# RotaryEncoderModule_r1_1.net
KiCad netlist of a schematic drawn in EAGLE
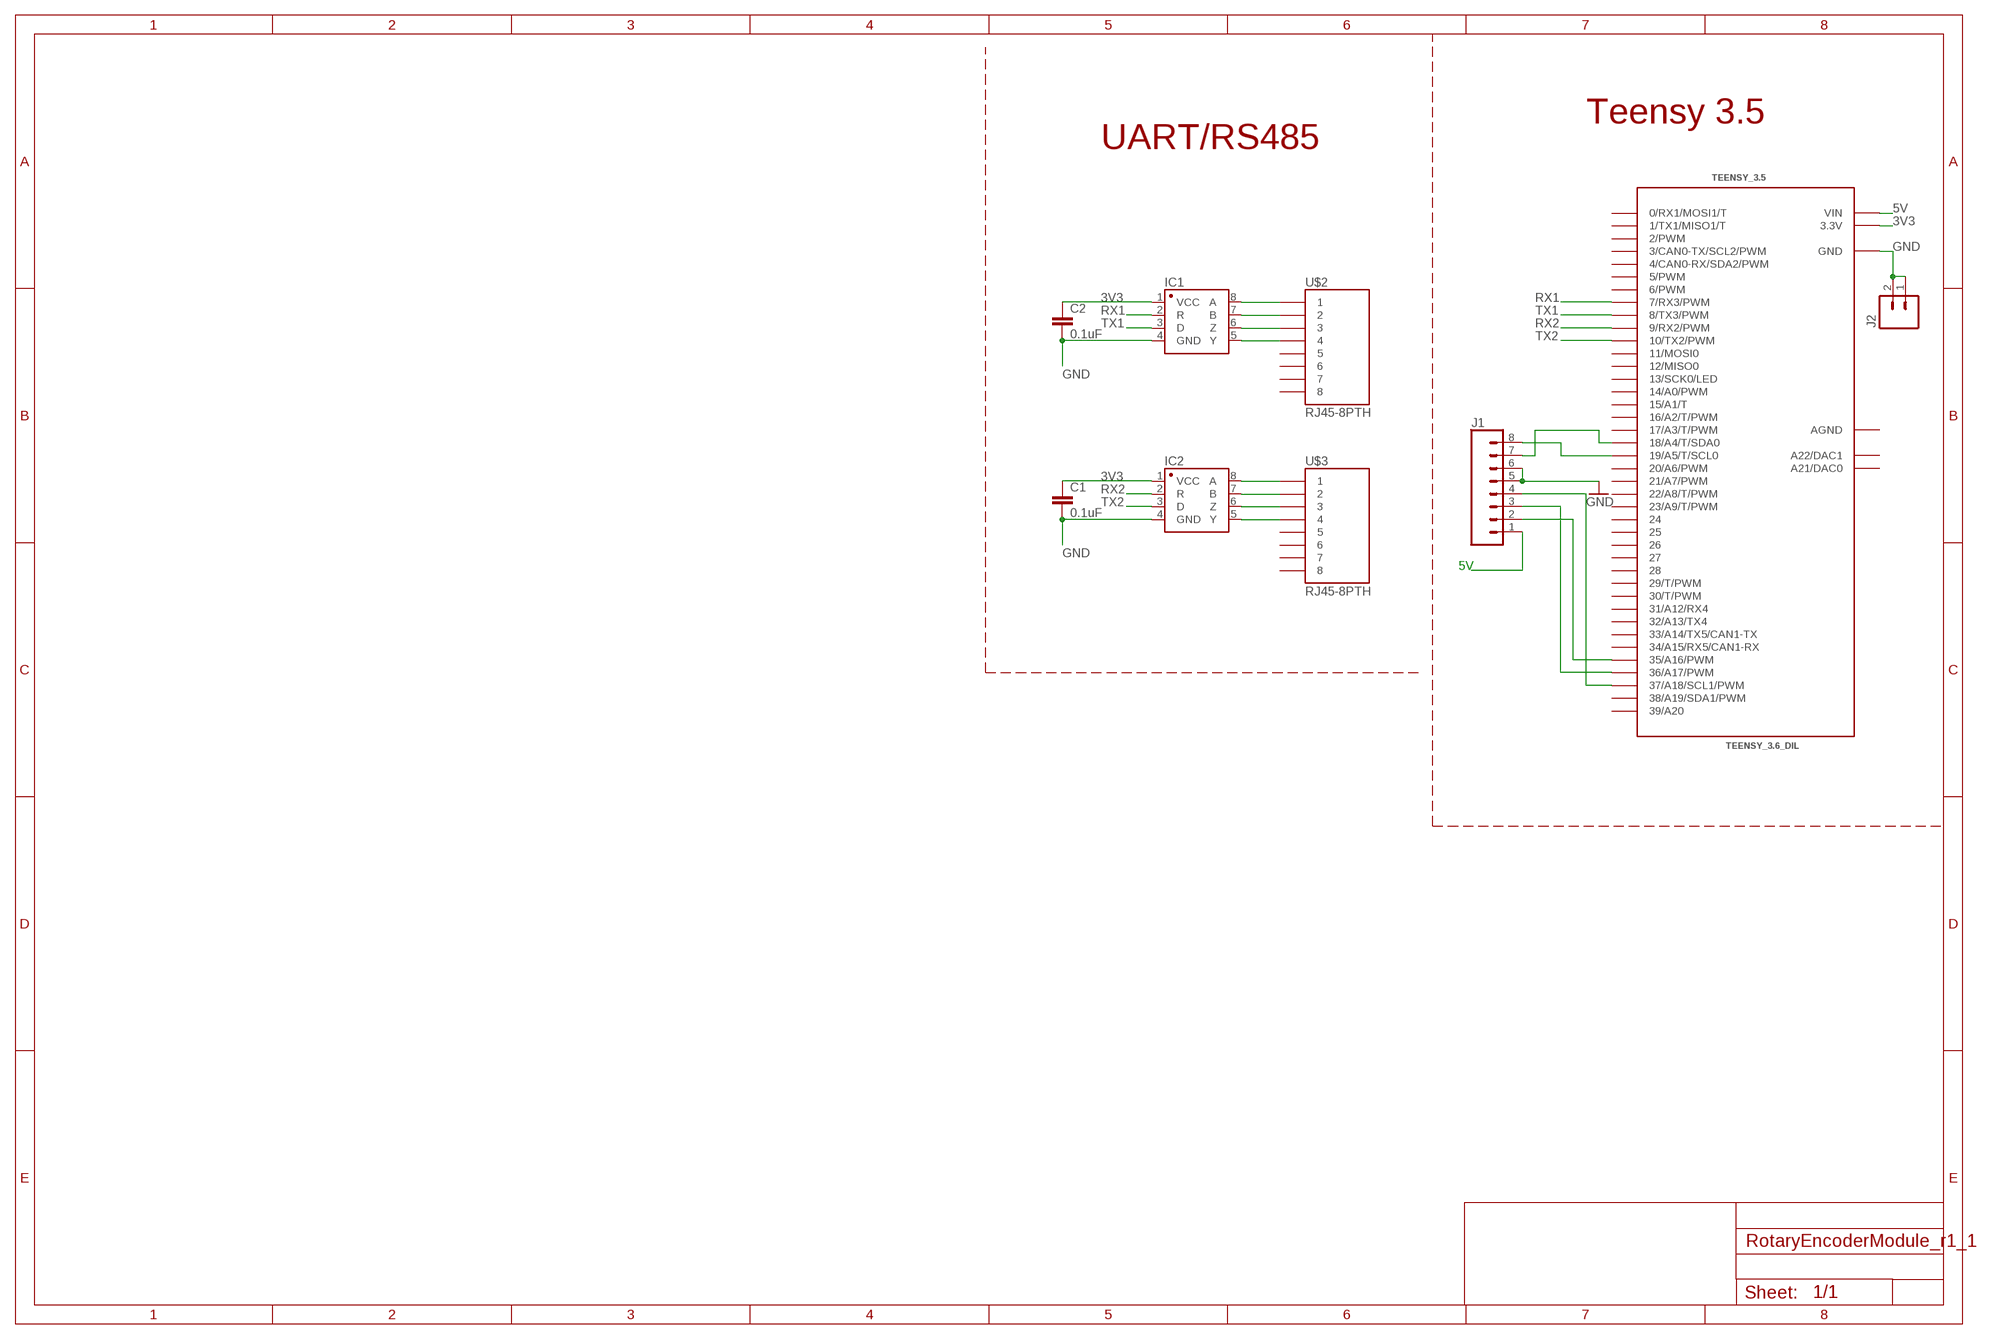
[diagram p0: schematic, sheet 1]

(export (version "E")
  (design (tool "Eeschema 10.0.6"))
  (components
    (comp (ref "C1")
      (value "0.1uF")
      (footprint "eagle-import:1206")
      (libsource (lib "eagle-import") (part "1.0UF-1206-50V-10%"))
    )
    (comp (ref "C2")
      (value "0.1uF")
      (footprint "eagle-import:1206")
      (libsource (lib "eagle-import") (part "1.0UF-1206-50V-10%"))
    )
    (comp (ref "IC1")
      (value "SN65HVD31DR")
      (footprint "eagle-import:SO08")
      (libsource (lib "eagle-import") (part "SN65HVD31DR"))
    )
    (comp (ref "IC2")
      (value "SN65HVD31DR")
      (footprint "eagle-import:SO08")
      (libsource (lib "eagle-import") (part "SN65HVD31DR"))
    )
    (comp (ref "J1")
      (value "CONN_083.5MM-8")
      (footprint "eagle-import:SCREWTERMINAL-3.5MM-8")
      (libsource (lib "eagle-import") (part "CONN_083.5MM-8"))
    )
    (comp (ref "J2")
      (value "M023.5MM")
      (footprint "eagle-import:SCREWTERMINAL-3.5MM-2")
      (libsource (lib "eagle-import") (part "M023.5MM"))
    )
    (comp (ref "TEENSY_3.5")
      (value "TEENSY_3.6_DIL")
      (footprint "eagle-import:TEENSY_3.6_DIL")
      (libsource (lib "eagle-import") (part "TEENSY_3.6_DIL"))
    )
    (comp (ref "U$2")
      (value "RJ45-8PTH")
      (footprint "eagle-import:RJ45-8")
      (libsource (lib "eagle-import") (part "RJ45-8PTH"))
    )
    (comp (ref "U$3")
      (value "RJ45-8PTH")
      (footprint "eagle-import:RJ45-8")
      (libsource (lib "eagle-import") (part "RJ45-8PTH"))
    )
  )
  (nets
    (net (code "1") (name "/3V3") (class "Default")
      (node (ref "C1") (pin "1") (pinfunction "1_1") (pintype "passive"))
      (node (ref "C2") (pin "1") (pinfunction "1_1") (pintype "passive"))
      (node (ref "IC1") (pin "1") (pinfunction "VCC_1") (pintype "bidirectional"))
      (node (ref "IC2") (pin "1") (pinfunction "VCC_1") (pintype "bidirectional"))
      (node (ref "TEENSY_3.5") (pin "3.3V") (pinfunction "3.3V_3.3V") (pintype "power_in"))
      (node (ref "TEENSY_3.5") (pin "3.3V3") (pinfunction "3.3V_3.3V3") (pintype "power_in"))
    )
    (net (code "2") (name "/5V") (class "Default")
      (node (ref "J1") (pin "1") (pinfunction "1_1") (pintype "passive"))
      (node (ref "TEENSY_3.5") (pin "VIN") (pinfunction "VIN_VIN") (pintype "power_in"))
    )
    (net (code "3") (name "/AGND") (class "Default")
      (node (ref "TEENSY_3.5") (pin "AGND") (pinfunction "AGND_AGND") (pintype "power_in"))
    )
    (net (code "4") (name "/RX1") (class "Default")
      (node (ref "IC1") (pin "2") (pinfunction "R_2") (pintype "bidirectional"))
      (node (ref "TEENSY_3.5") (pin "7") (pinfunction "7/RX3/PWM_7") (pintype "bidirectional"))
    )
    (net (code "5") (name "/RX2") (class "Default")
      (node (ref "IC2") (pin "2") (pinfunction "R_2") (pintype "bidirectional"))
      (node (ref "TEENSY_3.5") (pin "9") (pinfunction "9/RX2/PWM_9") (pintype "bidirectional"))
    )
    (net (code "6") (name "/TX1") (class "Default")
      (node (ref "IC1") (pin "3") (pinfunction "D_3") (pintype "bidirectional"))
      (node (ref "TEENSY_3.5") (pin "8") (pinfunction "8/TX3/PWM_8") (pintype "bidirectional"))
    )
    (net (code "7") (name "/TX2") (class "Default")
      (node (ref "IC2") (pin "3") (pinfunction "D_3") (pintype "bidirectional"))
      (node (ref "TEENSY_3.5") (pin "10") (pinfunction "10/TX2/PWM_10") (pintype "bidirectional"))
    )
    (net (code "8") (name "GND") (class "Default")
      (node (ref "C1") (pin "2") (pinfunction "2_2") (pintype "passive"))
      (node (ref "C2") (pin "2") (pinfunction "2_2") (pintype "passive"))
      (node (ref "IC1") (pin "4") (pinfunction "GND_4") (pintype "bidirectional"))
      (node (ref "IC2") (pin "4") (pinfunction "GND_4") (pintype "bidirectional"))
      (node (ref "J1") (pin "5") (pinfunction "5_5") (pintype "passive"))
      (node (ref "J1") (pin "6") (pinfunction "6_6") (pintype "passive"))
      (node (ref "J2") (pin "1") (pinfunction "1_1") (pintype "passive"))
      (node (ref "J2") (pin "2") (pinfunction "2_2") (pintype "passive"))
      (node (ref "TEENSY_3.5") (pin "GND") (pinfunction "GND_GND") (pintype "power_in"))
      (node (ref "TEENSY_3.5") (pin "GND1") (pinfunction "GND_GND1") (pintype "power_in"))
    )
    (net (code "9") (name "Net-(IC1-A)") (class "Default")
      (node (ref "IC1") (pin "8") (pinfunction "A_8") (pintype "bidirectional"))
      (node (ref "U$2") (pin "1") (pinfunction "1_1") (pintype "bidirectional"))
    )
    (net (code "10") (name "Net-(IC1-B)") (class "Default")
      (node (ref "IC1") (pin "7") (pinfunction "B_7") (pintype "bidirectional"))
      (node (ref "U$2") (pin "2") (pinfunction "2_2") (pintype "bidirectional"))
    )
    (net (code "11") (name "Net-(IC1-Y)") (class "Default")
      (node (ref "IC1") (pin "5") (pinfunction "Y_5") (pintype "bidirectional"))
      (node (ref "U$2") (pin "4") (pinfunction "4_4") (pintype "bidirectional"))
    )
    (net (code "12") (name "Net-(IC1-Z)") (class "Default")
      (node (ref "IC1") (pin "6") (pinfunction "Z_6") (pintype "bidirectional"))
      (node (ref "U$2") (pin "3") (pinfunction "3_3") (pintype "bidirectional"))
    )
    (net (code "13") (name "Net-(IC2-A)") (class "Default")
      (node (ref "IC2") (pin "8") (pinfunction "A_8") (pintype "bidirectional"))
      (node (ref "U$3") (pin "1") (pinfunction "1_1") (pintype "bidirectional"))
    )
    (net (code "14") (name "Net-(IC2-B)") (class "Default")
      (node (ref "IC2") (pin "7") (pinfunction "B_7") (pintype "bidirectional"))
      (node (ref "U$3") (pin "2") (pinfunction "2_2") (pintype "bidirectional"))
    )
    (net (code "15") (name "Net-(IC2-Y)") (class "Default")
      (node (ref "IC2") (pin "5") (pinfunction "Y_5") (pintype "bidirectional"))
      (node (ref "U$3") (pin "4") (pinfunction "4_4") (pintype "bidirectional"))
    )
    (net (code "16") (name "Net-(IC2-Z)") (class "Default")
      (node (ref "IC2") (pin "6") (pinfunction "Z_6") (pintype "bidirectional"))
      (node (ref "U$3") (pin "3") (pinfunction "3_3") (pintype "bidirectional"))
    )
    (net (code "17") (name "Net-(TEENSY_3.5-18{slash}A4{slash}T{slash}SDA0)") (class "Default")
      (node (ref "J1") (pin "7") (pinfunction "7_7") (pintype "passive"))
      (node (ref "TEENSY_3.5") (pin "18/A4") (pinfunction "18/A4/T/SDA0_18/A4") (pintype "bidirectional"))
    )
    (net (code "18") (name "Net-(TEENSY_3.5-19{slash}A5{slash}T{slash}SCL0)") (class "Default")
      (node (ref "J1") (pin "8") (pinfunction "8_8") (pintype "passive"))
      (node (ref "TEENSY_3.5") (pin "19/A5") (pinfunction "19/A5/T/SCL0_19/A5") (pintype "bidirectional"))
    )
    (net (code "19") (name "Net-(TEENSY_3.5-35{slash}A16{slash}PWM)") (class "Default")
      (node (ref "J1") (pin "2") (pinfunction "2_2") (pintype "passive"))
      (node (ref "TEENSY_3.5") (pin "35/A16") (pinfunction "35/A16/PWM_35/A16") (pintype "bidirectional"))
    )
    (net (code "20") (name "Net-(TEENSY_3.5-36{slash}A17{slash}PWM)") (class "Default")
      (node (ref "J1") (pin "3") (pinfunction "3_3") (pintype "passive"))
      (node (ref "TEENSY_3.5") (pin "36/A17") (pinfunction "36/A17/PWM_36/A17") (pintype "bidirectional"))
    )
    (net (code "21") (name "Net-(TEENSY_3.5-37{slash}A18{slash}SCL1{slash}PWM)") (class "Default")
      (node (ref "J1") (pin "4") (pinfunction "4_4") (pintype "passive"))
      (node (ref "TEENSY_3.5") (pin "37/A18") (pinfunction "37/A18/SCL1/PWM_37/A18") (pintype "bidirectional"))
    )
    (net (code "22") (name "unconnected-(TEENSY_3.5-0{slash}RX1{slash}MOSI1{slash}T-Pad0)") (class "Default")
      (node (ref "TEENSY_3.5") (pin "0") (pinfunction "0/RX1/MOSI1/T_0") (pintype "bidirectional"))
    )
    (net (code "23") (name "unconnected-(TEENSY_3.5-1{slash}TX1{slash}MISO1{slash}T-Pad1)") (class "Default")
      (node (ref "TEENSY_3.5") (pin "1") (pinfunction "1/TX1/MISO1/T_1") (pintype "bidirectional"))
    )
    (net (code "24") (name "unconnected-(TEENSY_3.5-2{slash}PWM-Pad2)") (class "Default")
      (node (ref "TEENSY_3.5") (pin "2") (pinfunction "2/PWM_2") (pintype "bidirectional"))
    )
    (net (code "25") (name "unconnected-(TEENSY_3.5-3{slash}CAN0-TX{slash}SCL2{slash}PWM-Pad3)") (class "Default")
      (node (ref "TEENSY_3.5") (pin "3") (pinfunction "3/CAN0-TX/SCL2/PWM_3") (pintype "bidirectional"))
    )
    (net (code "26") (name "unconnected-(TEENSY_3.5-4{slash}CAN0-RX{slash}SDA2{slash}PWM-Pad4)") (class "Default")
      (node (ref "TEENSY_3.5") (pin "4") (pinfunction "4/CAN0-RX/SDA2/PWM_4") (pintype "bidirectional"))
    )
    (net (code "27") (name "unconnected-(TEENSY_3.5-5{slash}PWM-Pad5)") (class "Default")
      (node (ref "TEENSY_3.5") (pin "5") (pinfunction "5/PWM_5") (pintype "bidirectional"))
    )
    (net (code "28") (name "unconnected-(TEENSY_3.5-6{slash}PWM-Pad6)") (class "Default")
      (node (ref "TEENSY_3.5") (pin "6") (pinfunction "6/PWM_6") (pintype "bidirectional"))
    )
    (net (code "29") (name "unconnected-(TEENSY_3.5-11{slash}MOSI0-Pad11)") (class "Default")
      (node (ref "TEENSY_3.5") (pin "11") (pinfunction "11/MOSI0_11") (pintype "bidirectional"))
    )
    (net (code "30") (name "unconnected-(TEENSY_3.5-12{slash}MISO0-Pad12)") (class "Default")
      (node (ref "TEENSY_3.5") (pin "12") (pinfunction "12/MISO0_12") (pintype "bidirectional"))
    )
    (net (code "31") (name "unconnected-(TEENSY_3.5-13{slash}SCK0{slash}LED-Pad13)") (class "Default")
      (node (ref "TEENSY_3.5") (pin "13") (pinfunction "13/SCK0/LED_13") (pintype "bidirectional"))
    )
    (net (code "32") (name "unconnected-(TEENSY_3.5-14{slash}A0{slash}PWM-Pad14{slash}A0)") (class "Default")
      (node (ref "TEENSY_3.5") (pin "14/A0") (pinfunction "14/A0/PWM_14/A0") (pintype "bidirectional"))
    )
    (net (code "33") (name "unconnected-(TEENSY_3.5-15{slash}A1{slash}T-Pad15{slash}A1)") (class "Default")
      (node (ref "TEENSY_3.5") (pin "15/A1") (pinfunction "15/A1/T_15/A1") (pintype "bidirectional"))
    )
    (net (code "34") (name "unconnected-(TEENSY_3.5-16{slash}A2{slash}T{slash}PWM-Pad16{slash}A2)") (class "Default")
      (node (ref "TEENSY_3.5") (pin "16/A2") (pinfunction "16/A2/T/PWM_16/A2") (pintype "bidirectional"))
    )
    (net (code "35") (name "unconnected-(TEENSY_3.5-17{slash}A3{slash}T{slash}PWM-Pad17{slash}A3)") (class "Default")
      (node (ref "TEENSY_3.5") (pin "17/A3") (pinfunction "17/A3/T/PWM_17/A3") (pintype "bidirectional"))
    )
    (net (code "36") (name "unconnected-(TEENSY_3.5-20{slash}A6{slash}PWM-Pad20{slash}A6)") (class "Default")
      (node (ref "TEENSY_3.5") (pin "20/A6") (pinfunction "20/A6/PWM_20/A6") (pintype "bidirectional"))
    )
    (net (code "37") (name "unconnected-(TEENSY_3.5-21{slash}A7{slash}PWM-Pad21{slash}A7)") (class "Default")
      (node (ref "TEENSY_3.5") (pin "21/A7") (pinfunction "21/A7/PWM_21/A7") (pintype "bidirectional"))
    )
    (net (code "38") (name "unconnected-(TEENSY_3.5-22{slash}A8{slash}T{slash}PWM-Pad22{slash}A8)") (class "Default")
      (node (ref "TEENSY_3.5") (pin "22/A8") (pinfunction "22/A8/T/PWM_22/A8") (pintype "bidirectional"))
    )
    (net (code "39") (name "unconnected-(TEENSY_3.5-23{slash}A9{slash}T{slash}PWM-Pad23{slash}A9)") (class "Default")
      (node (ref "TEENSY_3.5") (pin "23/A9") (pinfunction "23/A9/T/PWM_23/A9") (pintype "bidirectional"))
    )
    (net (code "40") (name "unconnected-(TEENSY_3.5-29{slash}T{slash}PWM-Pad29)") (class "Default")
      (node (ref "TEENSY_3.5") (pin "29") (pinfunction "29/T/PWM_29") (pintype "bidirectional"))
    )
    (net (code "41") (name "unconnected-(TEENSY_3.5-30{slash}T{slash}PWM-Pad30)") (class "Default")
      (node (ref "TEENSY_3.5") (pin "30") (pinfunction "30/T/PWM_30") (pintype "bidirectional"))
    )
    (net (code "42") (name "unconnected-(TEENSY_3.5-31{slash}A12{slash}RX4-Pad31{slash}A12)") (class "Default")
      (node (ref "TEENSY_3.5") (pin "31/A12") (pinfunction "31/A12/RX4_31/A12") (pintype "bidirectional"))
    )
    (net (code "43") (name "unconnected-(TEENSY_3.5-32{slash}A13{slash}TX4-Pad32{slash}A13)") (class "Default")
      (node (ref "TEENSY_3.5") (pin "32/A13") (pinfunction "32/A13/TX4_32/A13") (pintype "bidirectional"))
    )
    (net (code "44") (name "unconnected-(TEENSY_3.5-33{slash}A14{slash}TX5{slash}CAN1-TX-Pad33{slash}A14)") (class "Default")
      (node (ref "TEENSY_3.5") (pin "33/A14") (pinfunction "33/A14/TX5/CAN1-TX_33/A14") (pintype "bidirectional"))
    )
    (net (code "45") (name "unconnected-(TEENSY_3.5-34{slash}A15{slash}RX5{slash}CAN1-RX-Pad34{slash}A15)") (class "Default")
      (node (ref "TEENSY_3.5") (pin "34/A15") (pinfunction "34/A15/RX5/CAN1-RX_34/A15") (pintype "bidirectional"))
    )
    (net (code "46") (name "unconnected-(TEENSY_3.5-38{slash}A19{slash}SDA1{slash}PWM-Pad38{slash}A19)") (class "Default")
      (node (ref "TEENSY_3.5") (pin "38/A19") (pinfunction "38/A19/SDA1/PWM_38/A19") (pintype "bidirectional"))
    )
    (net (code "47") (name "unconnected-(TEENSY_3.5-A21{slash}DAC0-PadA21)") (class "Default")
      (node (ref "TEENSY_3.5") (pin "A21") (pinfunction "A21/DAC0_A21") (pintype "bidirectional"))
    )
    (net (code "48") (name "unconnected-(TEENSY_3.5-A22{slash}DAC1-PadA22)") (class "Default")
      (node (ref "TEENSY_3.5") (pin "A22") (pinfunction "A22/DAC1_A22") (pintype "bidirectional"))
    )
    (net (code "49") (name "unconnected-(TEENSY_3.5-Pad24)") (class "Default")
      (node (ref "TEENSY_3.5") (pin "24") (pinfunction "24_24") (pintype "bidirectional"))
    )
    (net (code "50") (name "unconnected-(TEENSY_3.5-Pad25)") (class "Default")
      (node (ref "TEENSY_3.5") (pin "25") (pinfunction "25_25") (pintype "bidirectional"))
    )
    (net (code "51") (name "unconnected-(TEENSY_3.5-Pad26)") (class "Default")
      (node (ref "TEENSY_3.5") (pin "26") (pinfunction "26_26") (pintype "bidirectional"))
    )
    (net (code "52") (name "unconnected-(TEENSY_3.5-Pad27)") (class "Default")
      (node (ref "TEENSY_3.5") (pin "27") (pinfunction "27_27") (pintype "bidirectional"))
    )
    (net (code "53") (name "unconnected-(TEENSY_3.5-Pad28)") (class "Default")
      (node (ref "TEENSY_3.5") (pin "28") (pinfunction "28_28") (pintype "bidirectional"))
    )
    (net (code "54") (name "unconnected-(TEENSY_3.5-Pad39{slash}A20)") (class "Default")
      (node (ref "TEENSY_3.5") (pin "39/A20") (pinfunction "39/A20_39/A20") (pintype "bidirectional"))
    )
    (net (code "55") (name "unconnected-(U$2-Pad5)") (class "Default")
      (node (ref "U$2") (pin "5") (pinfunction "5_5") (pintype "bidirectional"))
    )
    (net (code "56") (name "unconnected-(U$2-Pad6)") (class "Default")
      (node (ref "U$2") (pin "6") (pinfunction "6_6") (pintype "bidirectional"))
    )
    (net (code "57") (name "unconnected-(U$2-Pad7)") (class "Default")
      (node (ref "U$2") (pin "7") (pinfunction "7_7") (pintype "bidirectional"))
    )
    (net (code "58") (name "unconnected-(U$2-Pad8)") (class "Default")
      (node (ref "U$2") (pin "8") (pinfunction "8_8") (pintype "bidirectional"))
    )
    (net (code "59") (name "unconnected-(U$3-Pad5)") (class "Default")
      (node (ref "U$3") (pin "5") (pinfunction "5_5") (pintype "bidirectional"))
    )
    (net (code "60") (name "unconnected-(U$3-Pad6)") (class "Default")
      (node (ref "U$3") (pin "6") (pinfunction "6_6") (pintype "bidirectional"))
    )
    (net (code "61") (name "unconnected-(U$3-Pad7)") (class "Default")
      (node (ref "U$3") (pin "7") (pinfunction "7_7") (pintype "bidirectional"))
    )
    (net (code "62") (name "unconnected-(U$3-Pad8)") (class "Default")
      (node (ref "U$3") (pin "8") (pinfunction "8_8") (pintype "bidirectional"))
    )
  )
)
